# Sheet5.net
KiCad netlist of a schematic drawn in Altium Designer
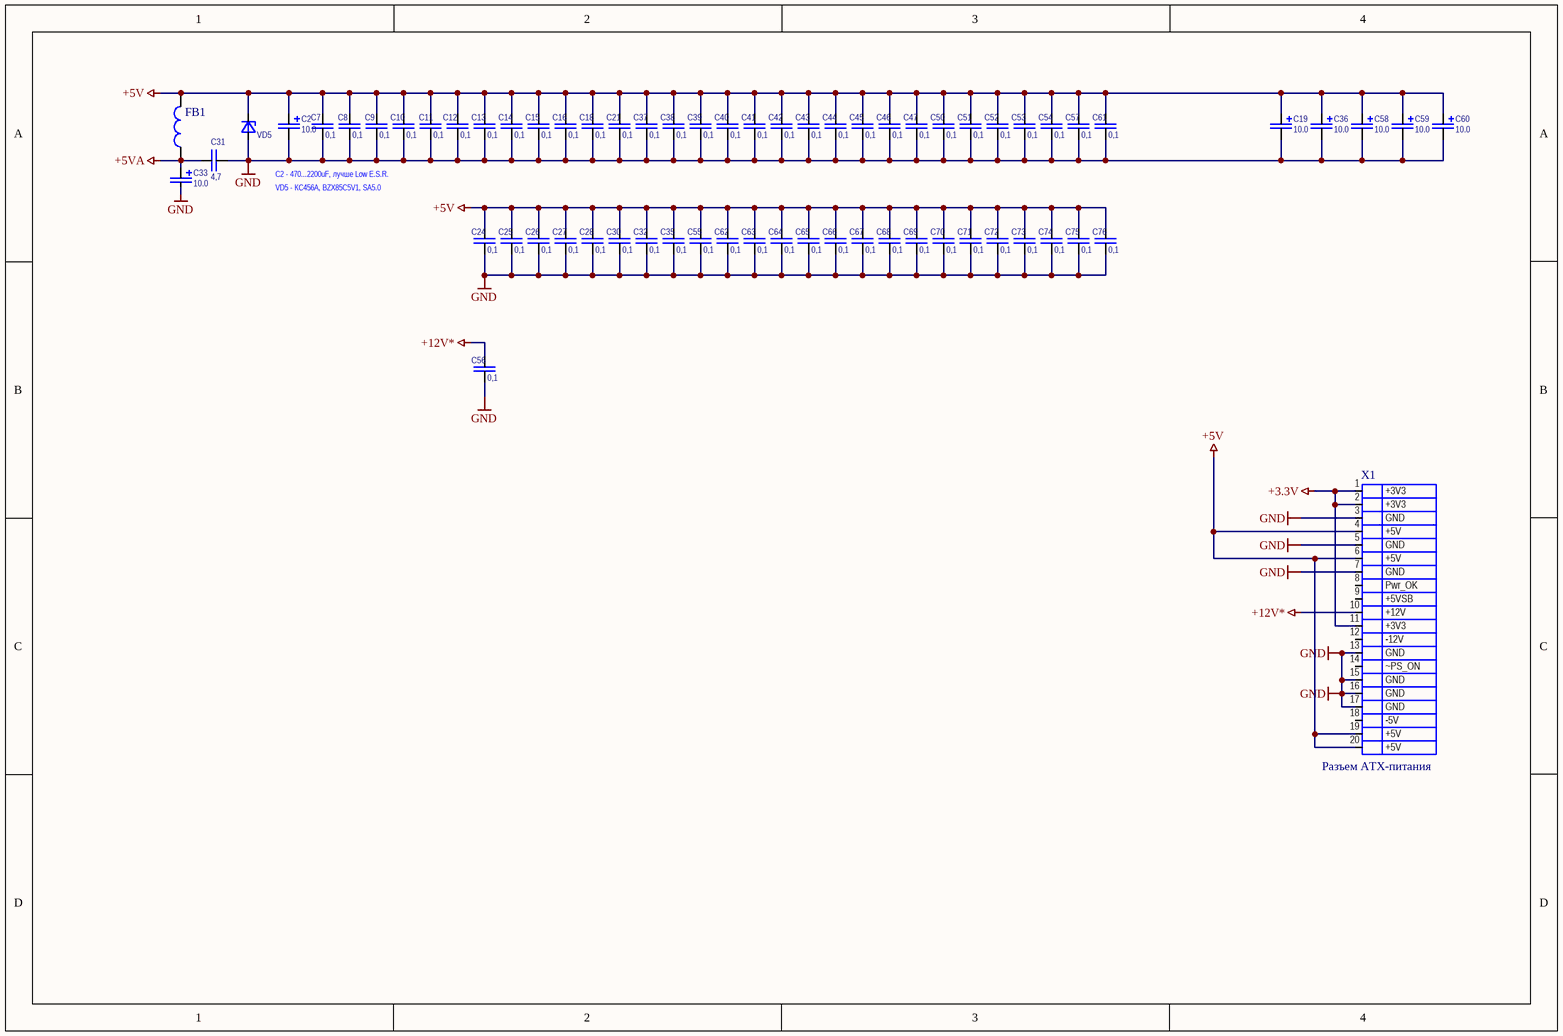
[diagram p0: Sheet5.SchDoc]

(export (version "E")
  (design (tool "Eeschema 10.0.6"))
  (components
    (comp (ref "C2")
      (value "10.0")
      (footprint "AL CAP P=5")
      (fields (field (name "Comment") "CP"))
      (libsource (lib "SchLib") (part "CP"))
    )
    (comp (ref "C7") (value "0,1") (footprint "CAP") (libsource (lib "SchLib") (part "C")))
    (comp (ref "C8") (value "0,1") (footprint "CAP") (libsource (lib "SchLib") (part "C")))
    (comp (ref "C9") (value "0,1") (footprint "CAP") (libsource (lib "SchLib") (part "C")))
    (comp (ref "C10") (value "0,1") (footprint "CAP") (libsource (lib "SchLib") (part "C")))
    (comp (ref "C11") (value "0,1") (footprint "CAP") (libsource (lib "SchLib") (part "C")))
    (comp (ref "C12") (value "0,1") (footprint "CAP") (libsource (lib "SchLib") (part "C")))
    (comp (ref "C13") (value "0,1") (footprint "CAP") (libsource (lib "SchLib") (part "C")))
    (comp (ref "C14") (value "0,1") (footprint "CAP") (libsource (lib "SchLib") (part "C")))
    (comp (ref "C15") (value "0,1") (footprint "CAP") (libsource (lib "SchLib") (part "C")))
    (comp (ref "C16") (value "0,1") (footprint "CAP") (libsource (lib "SchLib") (part "C")))
    (comp (ref "C18") (value "0,1") (footprint "CAP") (libsource (lib "SchLib") (part "C")))
    (comp (ref "C19")
      (value "10.0")
      (footprint "AL CAP P=2.5 D=3")
      (fields (field (name "Comment") "CP"))
      (libsource (lib "SchLib") (part "CP"))
    )
    (comp (ref "C21") (value "0,1") (footprint "CAP") (libsource (lib "SchLib") (part "C")))
    (comp (ref "C24") (value "0,1") (footprint "CAP") (libsource (lib "SchLib") (part "C")))
    (comp (ref "C25") (value "0,1") (footprint "CAP") (libsource (lib "SchLib") (part "C")))
    (comp (ref "C26") (value "0,1") (footprint "CAP") (libsource (lib "SchLib") (part "C")))
    (comp (ref "C27") (value "0,1") (footprint "CAP") (libsource (lib "SchLib") (part "C")))
    (comp (ref "C28") (value "0,1") (footprint "CAP") (libsource (lib "SchLib") (part "C")))
    (comp (ref "C30") (value "0,1") (footprint "CAP") (libsource (lib "SchLib") (part "C")))
    (comp (ref "C31") (value "4,7") (footprint "CAP") (libsource (lib "SchLib") (part "C")))
    (comp (ref "C32") (value "0,1") (footprint "CAP") (libsource (lib "SchLib") (part "C")))
    (comp (ref "C33")
      (value "10.0")
      (footprint "AL CAP P=2.5 D=3")
      (fields (field (name "Comment") "CP"))
      (libsource (lib "SchLib") (part "CP"))
    )
    (comp (ref "C35") (value "0,1") (footprint "CAP") (libsource (lib "SchLib") (part "C")))
    (comp (ref "C36")
      (value "10.0")
      (footprint "AL CAP P=2.5 D=3")
      (fields (field (name "Comment") "CP"))
      (libsource (lib "SchLib") (part "CP"))
    )
    (comp (ref "C37") (value "0,1") (footprint "CAP") (libsource (lib "SchLib") (part "C")))
    (comp (ref "C38") (value "0,1") (footprint "CAP") (libsource (lib "SchLib") (part "C")))
    (comp (ref "C39") (value "0,1") (footprint "CAP") (libsource (lib "SchLib") (part "C")))
    (comp (ref "C40") (value "0,1") (footprint "CAP") (libsource (lib "SchLib") (part "C")))
    (comp (ref "C41") (value "0,1") (footprint "CAP") (libsource (lib "SchLib") (part "C")))
    (comp (ref "C42") (value "0,1") (footprint "CAP") (libsource (lib "SchLib") (part "C")))
    (comp (ref "C43") (value "0,1") (footprint "CAP") (libsource (lib "SchLib") (part "C")))
    (comp (ref "C44") (value "0,1") (footprint "CAP") (libsource (lib "SchLib") (part "C")))
    (comp (ref "C45") (value "0,1") (footprint "CAP") (libsource (lib "SchLib") (part "C")))
    (comp (ref "C46") (value "0,1") (footprint "CAP") (libsource (lib "SchLib") (part "C")))
    (comp (ref "C47") (value "0,1") (footprint "CAP") (libsource (lib "SchLib") (part "C")))
    (comp (ref "C50") (value "0,1") (footprint "CAP") (libsource (lib "SchLib") (part "C")))
    (comp (ref "C51") (value "0,1") (footprint "CAP") (libsource (lib "SchLib") (part "C")))
    (comp (ref "C52") (value "0,1") (footprint "CAP") (libsource (lib "SchLib") (part "C")))
    (comp (ref "C53") (value "0,1") (footprint "CAP") (libsource (lib "SchLib") (part "C")))
    (comp (ref "C54") (value "0,1") (footprint "CAP") (libsource (lib "SchLib") (part "C")))
    (comp (ref "C55") (value "0,1") (footprint "CAP") (libsource (lib "SchLib") (part "C")))
    (comp (ref "C56") (value "0,1") (footprint "CAP") (libsource (lib "SchLib") (part "C")))
    (comp (ref "C57") (value "0,1") (footprint "CAP") (libsource (lib "SchLib") (part "C")))
    (comp (ref "C58")
      (value "10.0")
      (footprint "AL CAP P=2.5 D=3")
      (fields (field (name "Comment") "CP"))
      (libsource (lib "SchLib") (part "CP"))
    )
    (comp (ref "C59")
      (value "10.0")
      (footprint "AL CAP P=2.5 D=3")
      (fields (field (name "Comment") "CP"))
      (libsource (lib "SchLib") (part "CP"))
    )
    (comp (ref "C60")
      (value "10.0")
      (footprint "AL CAP P=2.5 D=3")
      (fields (field (name "Comment") "CP"))
      (libsource (lib "SchLib") (part "CP"))
    )
    (comp (ref "C61") (value "0,1") (footprint "CAP") (libsource (lib "SchLib") (part "C")))
    (comp (ref "C62") (value "0,1") (footprint "CAP") (libsource (lib "SchLib") (part "C")))
    (comp (ref "C63") (value "0,1") (footprint "CAP") (libsource (lib "SchLib") (part "C")))
    (comp (ref "C64") (value "0,1") (footprint "CAP") (libsource (lib "SchLib") (part "C")))
    (comp (ref "C65") (value "0,1") (footprint "CAP") (libsource (lib "SchLib") (part "C")))
    (comp (ref "C66") (value "0,1") (footprint "CAP") (libsource (lib "SchLib") (part "C")))
    (comp (ref "C67") (value "0,1") (footprint "CAP") (libsource (lib "SchLib") (part "C")))
    (comp (ref "C68") (value "0,1") (footprint "CAP") (libsource (lib "SchLib") (part "C")))
    (comp (ref "C69") (value "0,1") (footprint "CAP") (libsource (lib "SchLib") (part "C")))
    (comp (ref "C70") (value "0,1") (footprint "CAP") (libsource (lib "SchLib") (part "C")))
    (comp (ref "C71") (value "0,1") (footprint "CAP") (libsource (lib "SchLib") (part "C")))
    (comp (ref "C72") (value "0,1") (footprint "CAP") (libsource (lib "SchLib") (part "C")))
    (comp (ref "C73") (value "0,1") (footprint "CAP") (libsource (lib "SchLib") (part "C")))
    (comp (ref "C74") (value "0,1") (footprint "CAP") (libsource (lib "SchLib") (part "C")))
    (comp (ref "C75") (value "0,1") (footprint "CAP") (libsource (lib "SchLib") (part "C")))
    (comp (ref "C76") (value "0,1") (footprint "CAP") (libsource (lib "SchLib") (part "C")))
    (comp (ref "FB1") (value "FBEAD") (footprint "L AIXAL") (libsource (lib "SchLib") (part "FBEAD")))
    (comp (ref "VD5")
      (value "BZX85C5V1")
      (footprint "BZX85C5V1")
      (libsource (lib "SchLib") (part "BZX85C5V1"))
    )
    (comp (ref "X1")
      (value "Разъем ATX-питания")
      (footprint "ATXPOWER")
      (libsource (lib "SchLib") (part "ATX POWER CONN"))
    )
  )
  (nets
    (net (code "1") (name "+3.3V") (class "Default")
      (node (ref "X1") (pin "1") (pinfunction "+3V3_1") (pintype "passive"))
      (node (ref "X1") (pin "11") (pinfunction "+3V3_11") (pintype "passive"))
      (node (ref "X1") (pin "2") (pinfunction "+3V3_2") (pintype "passive"))
    )
    (net (code "2") (name "+5V") (class "Default")
      (node (ref "C10") (pin "1") (pintype "passive"))
      (node (ref "C11") (pin "1") (pintype "passive"))
      (node (ref "C12") (pin "1") (pintype "passive"))
      (node (ref "C13") (pin "1") (pintype "passive"))
      (node (ref "C14") (pin "1") (pintype "passive"))
      (node (ref "C15") (pin "1") (pintype "passive"))
      (node (ref "C16") (pin "1") (pintype "passive"))
      (node (ref "C18") (pin "1") (pintype "passive"))
      (node (ref "C19") (pin "1") (pintype "passive"))
      (node (ref "C2") (pin "1") (pintype "passive"))
      (node (ref "C21") (pin "1") (pintype "passive"))
      (node (ref "C24") (pin "1") (pintype "passive"))
      (node (ref "C25") (pin "1") (pintype "passive"))
      (node (ref "C26") (pin "1") (pintype "passive"))
      (node (ref "C27") (pin "1") (pintype "passive"))
      (node (ref "C28") (pin "1") (pintype "passive"))
      (node (ref "C30") (pin "1") (pintype "passive"))
      (node (ref "C32") (pin "1") (pintype "passive"))
      (node (ref "C35") (pin "1") (pintype "passive"))
      (node (ref "C36") (pin "1") (pintype "passive"))
      (node (ref "C37") (pin "1") (pintype "passive"))
      (node (ref "C38") (pin "1") (pintype "passive"))
      (node (ref "C39") (pin "1") (pintype "passive"))
      (node (ref "C40") (pin "1") (pintype "passive"))
      (node (ref "C41") (pin "1") (pintype "passive"))
      (node (ref "C42") (pin "1") (pintype "passive"))
      (node (ref "C43") (pin "1") (pintype "passive"))
      (node (ref "C44") (pin "1") (pintype "passive"))
      (node (ref "C45") (pin "1") (pintype "passive"))
      (node (ref "C46") (pin "1") (pintype "passive"))
      (node (ref "C47") (pin "1") (pintype "passive"))
      (node (ref "C50") (pin "1") (pintype "passive"))
      (node (ref "C51") (pin "1") (pintype "passive"))
      (node (ref "C52") (pin "1") (pintype "passive"))
      (node (ref "C53") (pin "1") (pintype "passive"))
      (node (ref "C54") (pin "1") (pintype "passive"))
      (node (ref "C55") (pin "1") (pintype "passive"))
      (node (ref "C57") (pin "1") (pintype "passive"))
      (node (ref "C58") (pin "1") (pintype "passive"))
      (node (ref "C59") (pin "1") (pintype "passive"))
      (node (ref "C60") (pin "1") (pintype "passive"))
      (node (ref "C61") (pin "1") (pintype "passive"))
      (node (ref "C62") (pin "1") (pintype "passive"))
      (node (ref "C63") (pin "1") (pintype "passive"))
      (node (ref "C64") (pin "1") (pintype "passive"))
      (node (ref "C65") (pin "1") (pintype "passive"))
      (node (ref "C66") (pin "1") (pintype "passive"))
      (node (ref "C67") (pin "1") (pintype "passive"))
      (node (ref "C68") (pin "1") (pintype "passive"))
      (node (ref "C69") (pin "1") (pintype "passive"))
      (node (ref "C7") (pin "1") (pintype "passive"))
      (node (ref "C70") (pin "1") (pintype "passive"))
      (node (ref "C71") (pin "1") (pintype "passive"))
      (node (ref "C72") (pin "1") (pintype "passive"))
      (node (ref "C73") (pin "1") (pintype "passive"))
      (node (ref "C74") (pin "1") (pintype "passive"))
      (node (ref "C75") (pin "1") (pintype "passive"))
      (node (ref "C76") (pin "1") (pintype "passive"))
      (node (ref "C8") (pin "1") (pintype "passive"))
      (node (ref "C9") (pin "1") (pintype "passive"))
      (node (ref "FB1") (pin "2") (pintype "passive"))
      (node (ref "VD5") (pin "2") (pintype "passive"))
      (node (ref "X1") (pin "19") (pinfunction "+5V_19") (pintype "passive"))
      (node (ref "X1") (pin "20") (pinfunction "+5V_20") (pintype "passive"))
      (node (ref "X1") (pin "4") (pinfunction "+5V_4") (pintype "passive"))
      (node (ref "X1") (pin "6") (pinfunction "+5V_6") (pintype "passive"))
    )
    (net (code "3") (name "+5VA") (class "Default")
      (node (ref "C31") (pin "1") (pintype "passive"))
      (node (ref "C33") (pin "1") (pintype "passive"))
      (node (ref "FB1") (pin "1") (pintype "passive"))
    )
    (net (code "4") (name "+12V*") (class "Default")
      (node (ref "C56") (pin "1") (pintype "passive"))
      (node (ref "X1") (pin "10") (pinfunction "+12V_10") (pintype "passive"))
    )
    (net (code "5") (name "GND") (class "Default")
      (node (ref "C10") (pin "2") (pintype "passive"))
      (node (ref "C11") (pin "2") (pintype "passive"))
      (node (ref "C12") (pin "2") (pintype "passive"))
      (node (ref "C13") (pin "2") (pintype "passive"))
      (node (ref "C14") (pin "2") (pintype "passive"))
      (node (ref "C15") (pin "2") (pintype "passive"))
      (node (ref "C16") (pin "2") (pintype "passive"))
      (node (ref "C18") (pin "2") (pintype "passive"))
      (node (ref "C19") (pin "2") (pintype "passive"))
      (node (ref "C2") (pin "2") (pintype "passive"))
      (node (ref "C21") (pin "2") (pintype "passive"))
      (node (ref "C24") (pin "2") (pintype "passive"))
      (node (ref "C25") (pin "2") (pintype "passive"))
      (node (ref "C26") (pin "2") (pintype "passive"))
      (node (ref "C27") (pin "2") (pintype "passive"))
      (node (ref "C28") (pin "2") (pintype "passive"))
      (node (ref "C30") (pin "2") (pintype "passive"))
      (node (ref "C31") (pin "2") (pintype "passive"))
      (node (ref "C32") (pin "2") (pintype "passive"))
      (node (ref "C33") (pin "2") (pintype "passive"))
      (node (ref "C35") (pin "2") (pintype "passive"))
      (node (ref "C36") (pin "2") (pintype "passive"))
      (node (ref "C37") (pin "2") (pintype "passive"))
      (node (ref "C38") (pin "2") (pintype "passive"))
      (node (ref "C39") (pin "2") (pintype "passive"))
      (node (ref "C40") (pin "2") (pintype "passive"))
      (node (ref "C41") (pin "2") (pintype "passive"))
      (node (ref "C42") (pin "2") (pintype "passive"))
      (node (ref "C43") (pin "2") (pintype "passive"))
      (node (ref "C44") (pin "2") (pintype "passive"))
      (node (ref "C45") (pin "2") (pintype "passive"))
      (node (ref "C46") (pin "2") (pintype "passive"))
      (node (ref "C47") (pin "2") (pintype "passive"))
      (node (ref "C50") (pin "2") (pintype "passive"))
      (node (ref "C51") (pin "2") (pintype "passive"))
      (node (ref "C52") (pin "2") (pintype "passive"))
      (node (ref "C53") (pin "2") (pintype "passive"))
      (node (ref "C54") (pin "2") (pintype "passive"))
      (node (ref "C55") (pin "2") (pintype "passive"))
      (node (ref "C56") (pin "2") (pintype "passive"))
      (node (ref "C57") (pin "2") (pintype "passive"))
      (node (ref "C58") (pin "2") (pintype "passive"))
      (node (ref "C59") (pin "2") (pintype "passive"))
      (node (ref "C60") (pin "2") (pintype "passive"))
      (node (ref "C61") (pin "2") (pintype "passive"))
      (node (ref "C62") (pin "2") (pintype "passive"))
      (node (ref "C63") (pin "2") (pintype "passive"))
      (node (ref "C64") (pin "2") (pintype "passive"))
      (node (ref "C65") (pin "2") (pintype "passive"))
      (node (ref "C66") (pin "2") (pintype "passive"))
      (node (ref "C67") (pin "2") (pintype "passive"))
      (node (ref "C68") (pin "2") (pintype "passive"))
      (node (ref "C69") (pin "2") (pintype "passive"))
      (node (ref "C7") (pin "2") (pintype "passive"))
      (node (ref "C70") (pin "2") (pintype "passive"))
      (node (ref "C71") (pin "2") (pintype "passive"))
      (node (ref "C72") (pin "2") (pintype "passive"))
      (node (ref "C73") (pin "2") (pintype "passive"))
      (node (ref "C74") (pin "2") (pintype "passive"))
      (node (ref "C75") (pin "2") (pintype "passive"))
      (node (ref "C76") (pin "2") (pintype "passive"))
      (node (ref "C8") (pin "2") (pintype "passive"))
      (node (ref "C9") (pin "2") (pintype "passive"))
      (node (ref "VD5") (pin "1") (pintype "passive"))
      (node (ref "X1") (pin "13") (pinfunction "GND_13") (pintype "passive"))
      (node (ref "X1") (pin "15") (pinfunction "GND_15") (pintype "passive"))
      (node (ref "X1") (pin "16") (pinfunction "GND_16") (pintype "passive"))
      (node (ref "X1") (pin "17") (pinfunction "GND_17") (pintype "passive"))
      (node (ref "X1") (pin "3") (pinfunction "GND_3") (pintype "passive"))
      (node (ref "X1") (pin "5") (pinfunction "GND_5") (pintype "passive"))
      (node (ref "X1") (pin "7") (pinfunction "GND_7") (pintype "passive"))
    )
    (net (code "6") (name "unconnected-(X1-+5VSB-Pad9)") (class "Default")
      (node (ref "X1") (pin "9") (pinfunction "+5VSB_9") (pintype "passive"))
    )
    (net (code "7") (name "unconnected-(X1--5V-Pad18)") (class "Default")
      (node (ref "X1") (pin "18") (pinfunction "-5V_18") (pintype "passive"))
    )
    (net (code "8") (name "unconnected-(X1--12V-Pad12)") (class "Default")
      (node (ref "X1") (pin "12") (pinfunction "-12V_12") (pintype "passive"))
    )
    (net (code "9") (name "unconnected-(X1-Pwr_OK-Pad8)") (class "Default")
      (node (ref "X1") (pin "8") (pinfunction "Pwr_OK_8") (pintype "passive"))
    )
    (net (code "10") (name "unconnected-(X1-~PS_ON-Pad14)") (class "Default")
      (node (ref "X1") (pin "14") (pinfunction "~PS_ON_14") (pintype "passive"))
    )
  )
)
